# psg-single-ad9833.net
KiCad netlist of a schematic drawn in EAGLE
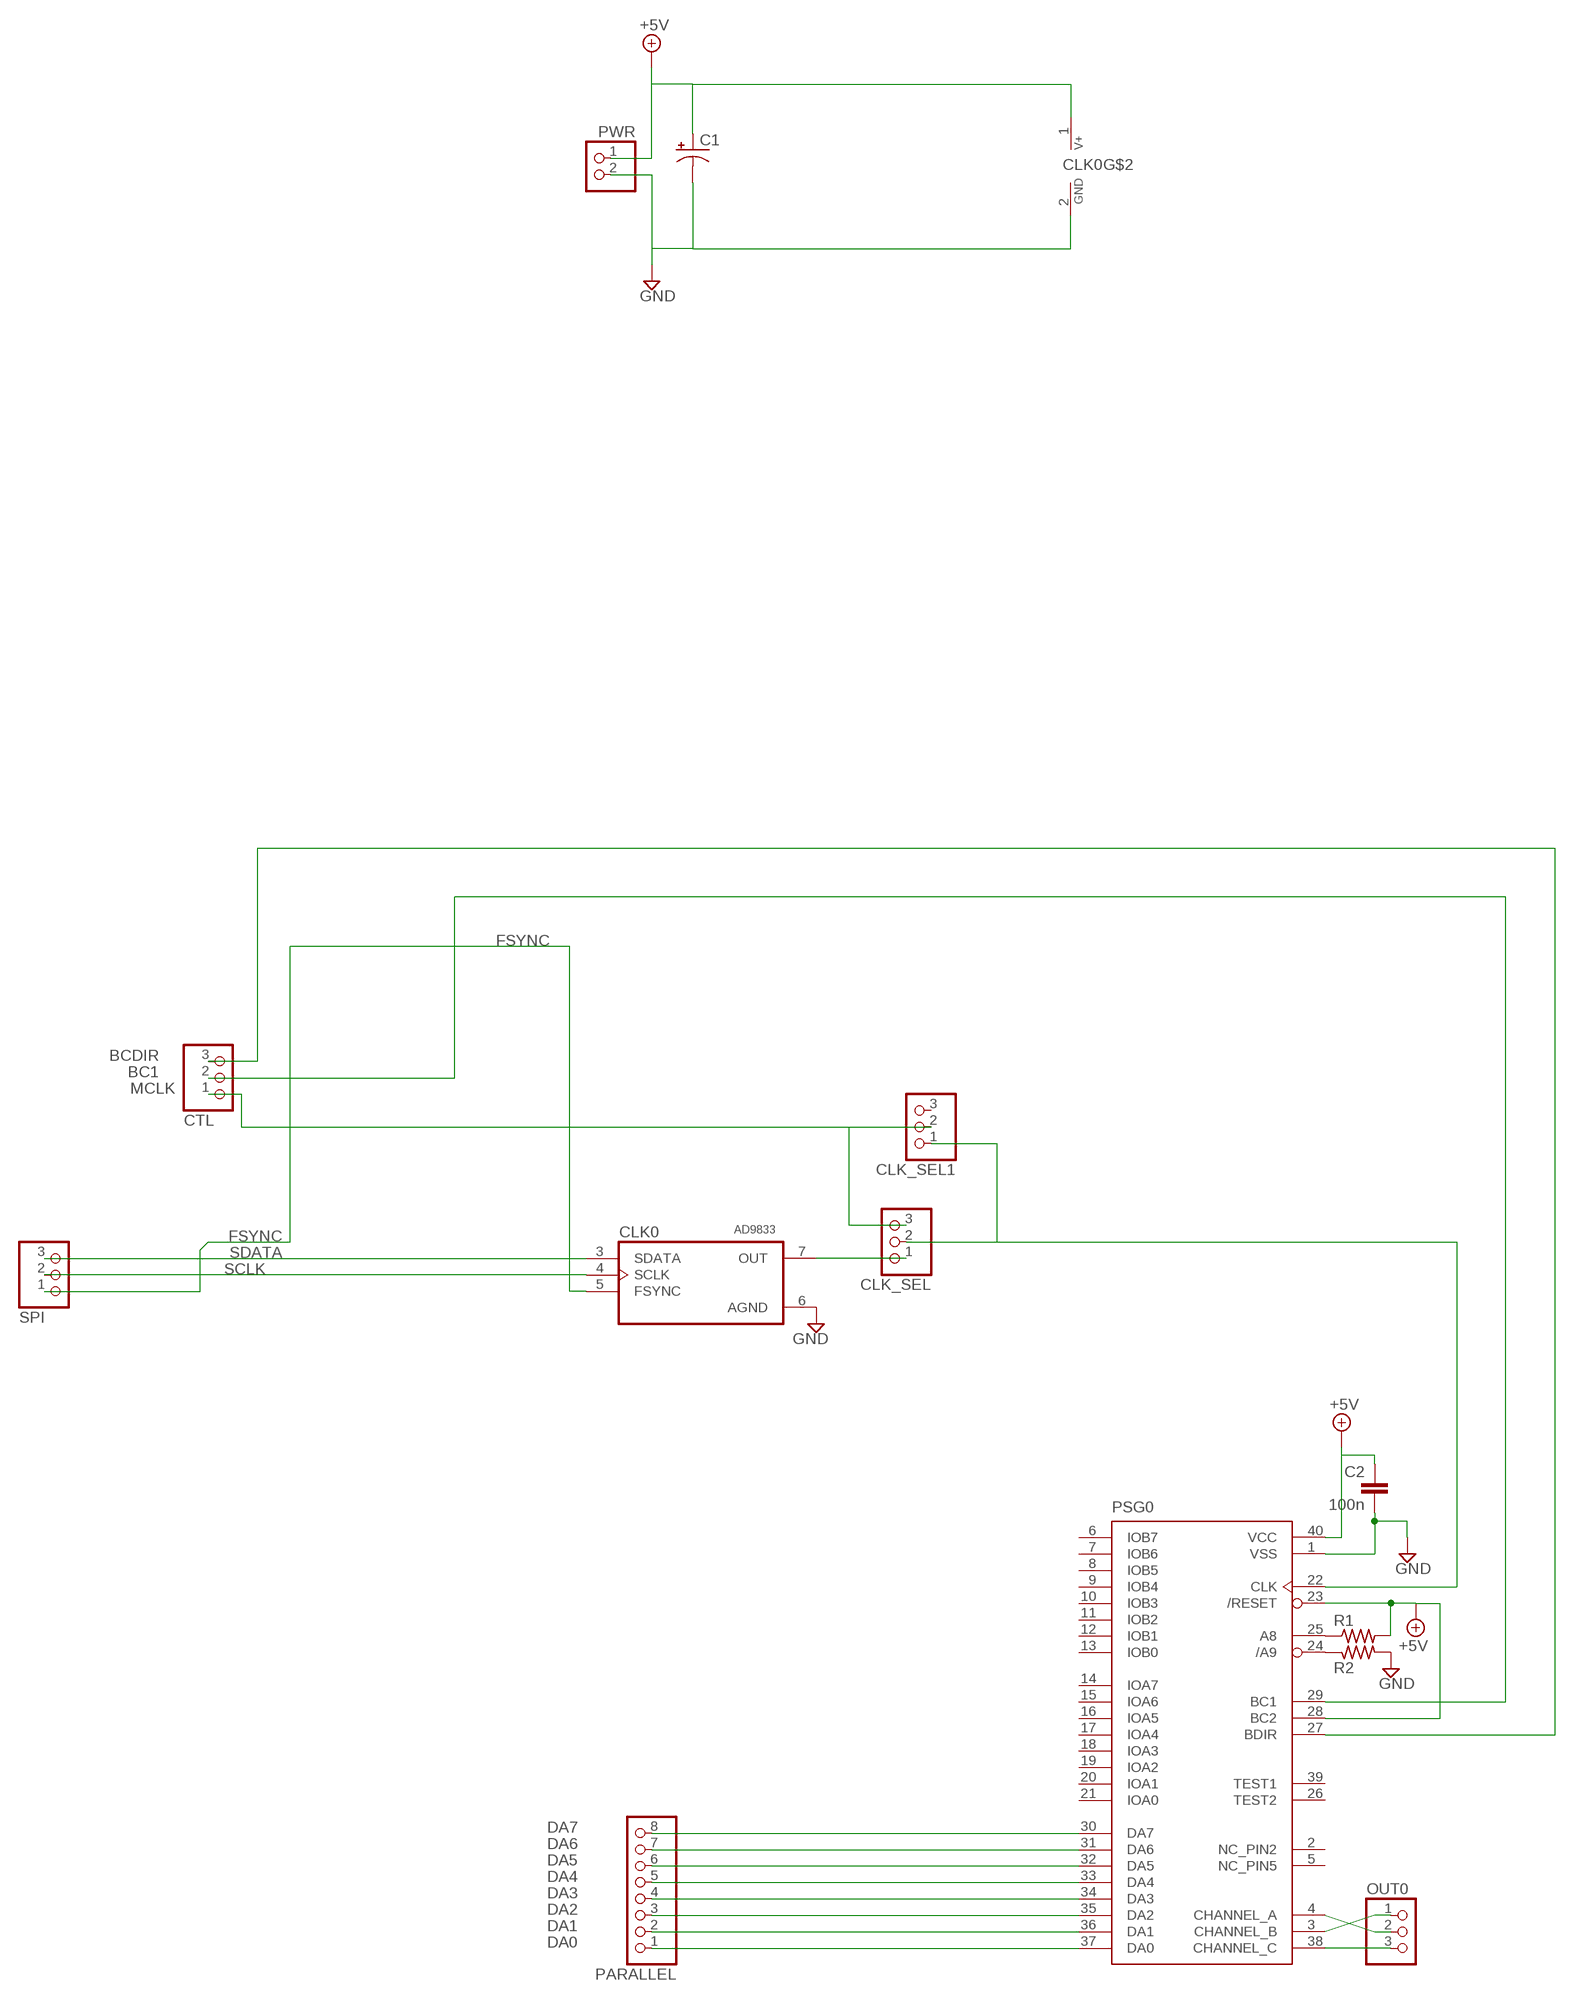
[diagram p0: schematic, sheet 1]

(export (version "E")
  (design (tool "Eeschema 10.0.6"))
  (components
    (comp (ref "C1")
      (value "0501")
      (footprint "eagle-import:050_020_1")
      (libsource (lib "eagle-import") (part "0501"))
    )
    (comp (ref "C2")
      (value "100n")
      (footprint "eagle-import:050X030_025")
      (libsource (lib "eagle-import") (part "050X030_0251"))
    )
    (comp (ref "CLK0")
      (value "AD9833_MODULE")
      (footprint "eagle-import:AD9833_MODULE")
      (libsource (lib "eagle-import") (part "AD9833_MODULE"))
    )
    (comp (ref "CLK_SEL")
      (value "PINHD-1X3/90")
      (footprint "eagle-import:1X03_90")
      (libsource (lib "eagle-import") (part "PINHD-1X3/90"))
    )
    (comp (ref "CLK_SEL1")
      (value "PINHD-1X3/90")
      (footprint "eagle-import:1X03_90")
      (libsource (lib "eagle-import") (part "PINHD-1X3/90"))
    )
    (comp (ref "CTL")
      (value "PINHD-1X3/90")
      (footprint "eagle-import:1X03_90")
      (libsource (lib "eagle-import") (part "PINHD-1X3/90"))
    )
    (comp (ref "OUT0")
      (value "PINHD-1X3/90")
      (footprint "eagle-import:1X03_90")
      (libsource (lib "eagle-import") (part "PINHD-1X3/90"))
    )
    (comp (ref "PARALLEL")
      (value "PINHD-1X8/90")
      (footprint "eagle-import:1X08_90")
      (libsource (lib "eagle-import") (part "PINHD-1X8/90"))
    )
    (comp (ref "PSG0")
      (value "AY-3-8910")
      (footprint "eagle-import:DIL40")
      (libsource (lib "eagle-import") (part "AY-3-8910"))
    )
    (comp (ref "PWR")
      (value "PINHD-1X2/90")
      (footprint "eagle-import:1X02_90")
      (libsource (lib "eagle-import") (part "PINHD-1X2/90"))
    )
    (comp (ref "R1")
      (value "6MM.3")
      (footprint "eagle-import:R0207_3")
      (libsource (lib "eagle-import") (part "6MM.3"))
    )
    (comp (ref "R2")
      (value "6MM.3")
      (footprint "eagle-import:R0207_3")
      (libsource (lib "eagle-import") (part "6MM.3"))
    )
    (comp (ref "SPI")
      (value "PINHD-1X3/90")
      (footprint "eagle-import:1X03_90")
      (libsource (lib "eagle-import") (part "PINHD-1X3/90"))
    )
  )
  (nets
    (net (code "1") (name "+5V") (class "Default")
      (node (ref "C1") (pin "+") (pinfunction "+_+") (pintype "passive"))
      (node (ref "C2") (pin "1") (pinfunction "1_1") (pintype "passive"))
      (node (ref "CLK0") (pin "1") (pinfunction "+V_1") (pintype "power_in"))
      (node (ref "PSG0") (pin "23") (pinfunction "/RESET_23") (pintype "input"))
      (node (ref "PSG0") (pin "28") (pinfunction "BC2_28") (pintype "input"))
      (node (ref "PSG0") (pin "40") (pinfunction "VCC_40") (pintype "power_in"))
      (node (ref "PWR") (pin "1") (pinfunction "1_1") (pintype "passive"))
      (node (ref "R1") (pin "2") (pinfunction "2_2") (pintype "passive"))
    )
    (net (code "2") (name "/BC1") (class "Default")
      (node (ref "CTL") (pin "2") (pinfunction "2_2") (pintype "passive"))
      (node (ref "PSG0") (pin "29") (pinfunction "BC1_29") (pintype "input"))
    )
    (net (code "3") (name "/BCDIR") (class "Default")
      (node (ref "CTL") (pin "3") (pinfunction "3_3") (pintype "passive"))
      (node (ref "PSG0") (pin "27") (pinfunction "BDIR_27") (pintype "input"))
    )
    (net (code "4") (name "/DA0") (class "Default")
      (node (ref "PARALLEL") (pin "1") (pinfunction "1_1") (pintype "passive"))
      (node (ref "PSG0") (pin "37") (pinfunction "DA0_37") (pintype "bidirectional"))
    )
    (net (code "5") (name "/DA1") (class "Default")
      (node (ref "PARALLEL") (pin "2") (pinfunction "2_2") (pintype "passive"))
      (node (ref "PSG0") (pin "36") (pinfunction "DA1_36") (pintype "bidirectional"))
    )
    (net (code "6") (name "/DA2") (class "Default")
      (node (ref "PARALLEL") (pin "3") (pinfunction "3_3") (pintype "passive"))
      (node (ref "PSG0") (pin "35") (pinfunction "DA2_35") (pintype "bidirectional"))
    )
    (net (code "7") (name "/DA3") (class "Default")
      (node (ref "PARALLEL") (pin "4") (pinfunction "4_4") (pintype "passive"))
      (node (ref "PSG0") (pin "34") (pinfunction "DA3_34") (pintype "bidirectional"))
    )
    (net (code "8") (name "/DA4") (class "Default")
      (node (ref "PARALLEL") (pin "5") (pinfunction "5_5") (pintype "passive"))
      (node (ref "PSG0") (pin "33") (pinfunction "DA4_33") (pintype "bidirectional"))
    )
    (net (code "9") (name "/DA5") (class "Default")
      (node (ref "PARALLEL") (pin "6") (pinfunction "6_6") (pintype "passive"))
      (node (ref "PSG0") (pin "32") (pinfunction "DA5_32") (pintype "bidirectional"))
    )
    (net (code "10") (name "/DA6") (class "Default")
      (node (ref "PARALLEL") (pin "7") (pinfunction "7_7") (pintype "passive"))
      (node (ref "PSG0") (pin "31") (pinfunction "DA6_31") (pintype "bidirectional"))
    )
    (net (code "11") (name "/DA7") (class "Default")
      (node (ref "PARALLEL") (pin "8") (pinfunction "8_8") (pintype "passive"))
      (node (ref "PSG0") (pin "30") (pinfunction "DA7_30") (pintype "bidirectional"))
    )
    (net (code "12") (name "/FSYNC") (class "Default")
      (node (ref "CLK0") (pin "5") (pinfunction "FSYNC_5") (pintype "input"))
      (node (ref "SPI") (pin "1") (pinfunction "1_1") (pintype "passive"))
    )
    (net (code "13") (name "/MCLK") (class "Default")
      (node (ref "CLK_SEL") (pin "3") (pinfunction "3_3") (pintype "passive"))
      (node (ref "CLK_SEL1") (pin "2") (pinfunction "2_2") (pintype "passive"))
      (node (ref "CTL") (pin "1") (pinfunction "1_1") (pintype "passive"))
    )
    (net (code "14") (name "/SCLK") (class "Default")
      (node (ref "CLK0") (pin "4") (pinfunction "SCLK_4") (pintype "input"))
      (node (ref "SPI") (pin "2") (pinfunction "2_2") (pintype "passive"))
    )
    (net (code "15") (name "/SDATA") (class "Default")
      (node (ref "CLK0") (pin "3") (pinfunction "SDATA_3") (pintype "bidirectional"))
      (node (ref "SPI") (pin "3") (pinfunction "3_3") (pintype "passive"))
    )
    (net (code "16") (name "GND") (class "Default")
      (node (ref "C1") (pin "-") (pinfunction "-_-") (pintype "passive"))
      (node (ref "C2") (pin "2") (pinfunction "2_2") (pintype "passive"))
      (node (ref "CLK0") (pin "2") (pinfunction "GND_2") (pintype "power_in"))
      (node (ref "CLK0") (pin "6") (pinfunction "AGND_6") (pintype "power_in"))
      (node (ref "PSG0") (pin "1") (pinfunction "VSS_1") (pintype "power_in"))
      (node (ref "PWR") (pin "2") (pinfunction "2_2") (pintype "passive"))
      (node (ref "R2") (pin "2") (pinfunction "2_2") (pintype "passive"))
    )
    (net (code "17") (name "Net-(CLK0A-OUT)") (class "Default")
      (node (ref "CLK0") (pin "7") (pinfunction "OUT_7") (pintype "output"))
      (node (ref "CLK_SEL") (pin "1") (pinfunction "1_1") (pintype "passive"))
    )
    (net (code "18") (name "Net-(PSG0-A8)") (class "Default")
      (node (ref "PSG0") (pin "25") (pinfunction "A8_25") (pintype "bidirectional"))
      (node (ref "R1") (pin "1") (pinfunction "1_1") (pintype "passive"))
    )
    (net (code "19") (name "Net-(PSG0-CHANNEL_A)") (class "Default")
      (node (ref "OUT0") (pin "2") (pinfunction "2_2") (pintype "passive"))
      (node (ref "PSG0") (pin "4") (pinfunction "CHANNEL_A_4") (pintype "output"))
    )
    (net (code "20") (name "Net-(PSG0-CHANNEL_B)") (class "Default")
      (node (ref "OUT0") (pin "1") (pinfunction "1_1") (pintype "passive"))
      (node (ref "PSG0") (pin "3") (pinfunction "CHANNEL_B_3") (pintype "output"))
    )
    (net (code "21") (name "Net-(PSG0-CHANNEL_C)") (class "Default")
      (node (ref "OUT0") (pin "3") (pinfunction "3_3") (pintype "passive"))
      (node (ref "PSG0") (pin "38") (pinfunction "CHANNEL_C_38") (pintype "output"))
    )
    (net (code "22") (name "Net-(PSG0-CLK)") (class "Default")
      (node (ref "CLK_SEL") (pin "2") (pinfunction "2_2") (pintype "passive"))
      (node (ref "CLK_SEL1") (pin "1") (pinfunction "1_1") (pintype "passive"))
      (node (ref "PSG0") (pin "22") (pinfunction "CLK_22") (pintype "input"))
    )
    (net (code "23") (name "Net-(PSG0-{slash}A9)") (class "Default")
      (node (ref "PSG0") (pin "24") (pinfunction "/A9_24") (pintype "bidirectional"))
      (node (ref "R2") (pin "1") (pinfunction "1_1") (pintype "passive"))
    )
    (net (code "24") (name "unconnected-(CLK_SEL1-Pad3)") (class "Default")
      (node (ref "CLK_SEL1") (pin "3") (pinfunction "3_3") (pintype "passive"))
    )
    (net (code "25") (name "unconnected-(PSG0-IOA0-Pad21)") (class "Default")
      (node (ref "PSG0") (pin "21") (pinfunction "IOA0_21") (pintype "bidirectional"))
    )
    (net (code "26") (name "unconnected-(PSG0-IOA1-Pad20)") (class "Default")
      (node (ref "PSG0") (pin "20") (pinfunction "IOA1_20") (pintype "bidirectional"))
    )
    (net (code "27") (name "unconnected-(PSG0-IOA2-Pad19)") (class "Default")
      (node (ref "PSG0") (pin "19") (pinfunction "IOA2_19") (pintype "bidirectional"))
    )
    (net (code "28") (name "unconnected-(PSG0-IOA3-Pad18)") (class "Default")
      (node (ref "PSG0") (pin "18") (pinfunction "IOA3_18") (pintype "bidirectional"))
    )
    (net (code "29") (name "unconnected-(PSG0-IOA4-Pad17)") (class "Default")
      (node (ref "PSG0") (pin "17") (pinfunction "IOA4_17") (pintype "bidirectional"))
    )
    (net (code "30") (name "unconnected-(PSG0-IOA5-Pad16)") (class "Default")
      (node (ref "PSG0") (pin "16") (pinfunction "IOA5_16") (pintype "bidirectional"))
    )
    (net (code "31") (name "unconnected-(PSG0-IOA6-Pad15)") (class "Default")
      (node (ref "PSG0") (pin "15") (pinfunction "IOA6_15") (pintype "bidirectional"))
    )
    (net (code "32") (name "unconnected-(PSG0-IOA7-Pad14)") (class "Default")
      (node (ref "PSG0") (pin "14") (pinfunction "IOA7_14") (pintype "bidirectional"))
    )
    (net (code "33") (name "unconnected-(PSG0-IOB0-Pad13)") (class "Default")
      (node (ref "PSG0") (pin "13") (pinfunction "IOB0_13") (pintype "bidirectional"))
    )
    (net (code "34") (name "unconnected-(PSG0-IOB1-Pad12)") (class "Default")
      (node (ref "PSG0") (pin "12") (pinfunction "IOB1_12") (pintype "bidirectional"))
    )
    (net (code "35") (name "unconnected-(PSG0-IOB2-Pad11)") (class "Default")
      (node (ref "PSG0") (pin "11") (pinfunction "IOB2_11") (pintype "bidirectional"))
    )
    (net (code "36") (name "unconnected-(PSG0-IOB3-Pad10)") (class "Default")
      (node (ref "PSG0") (pin "10") (pinfunction "IOB3_10") (pintype "bidirectional"))
    )
    (net (code "37") (name "unconnected-(PSG0-IOB4-Pad9)") (class "Default")
      (node (ref "PSG0") (pin "9") (pinfunction "IOB4_9") (pintype "bidirectional"))
    )
    (net (code "38") (name "unconnected-(PSG0-IOB5-Pad8)") (class "Default")
      (node (ref "PSG0") (pin "8") (pinfunction "IOB5_8") (pintype "bidirectional"))
    )
    (net (code "39") (name "unconnected-(PSG0-IOB6-Pad7)") (class "Default")
      (node (ref "PSG0") (pin "7") (pinfunction "IOB6_7") (pintype "bidirectional"))
    )
    (net (code "40") (name "unconnected-(PSG0-IOB7-Pad6)") (class "Default")
      (node (ref "PSG0") (pin "6") (pinfunction "IOB7_6") (pintype "bidirectional"))
    )
    (net (code "41") (name "unconnected-(PSG0-NC_PIN2-Pad2)") (class "Default")
      (node (ref "PSG0") (pin "2") (pinfunction "NC_PIN2_2") (pintype "no_connect"))
    )
    (net (code "42") (name "unconnected-(PSG0-NC_PIN5-Pad5)") (class "Default")
      (node (ref "PSG0") (pin "5") (pinfunction "NC_PIN5_5") (pintype "bidirectional"))
    )
    (net (code "43") (name "unconnected-(PSG0-TEST1-Pad39)") (class "Default")
      (node (ref "PSG0") (pin "39") (pinfunction "TEST1_39") (pintype "no_connect"))
    )
    (net (code "44") (name "unconnected-(PSG0-TEST2-Pad26)") (class "Default")
      (node (ref "PSG0") (pin "26") (pinfunction "TEST2_26") (pintype "no_connect"))
    )
  )
)
